# rw-fet-cc-24mm-mk-1_0_1.net
KiCad netlist of a schematic drawn in EAGLE
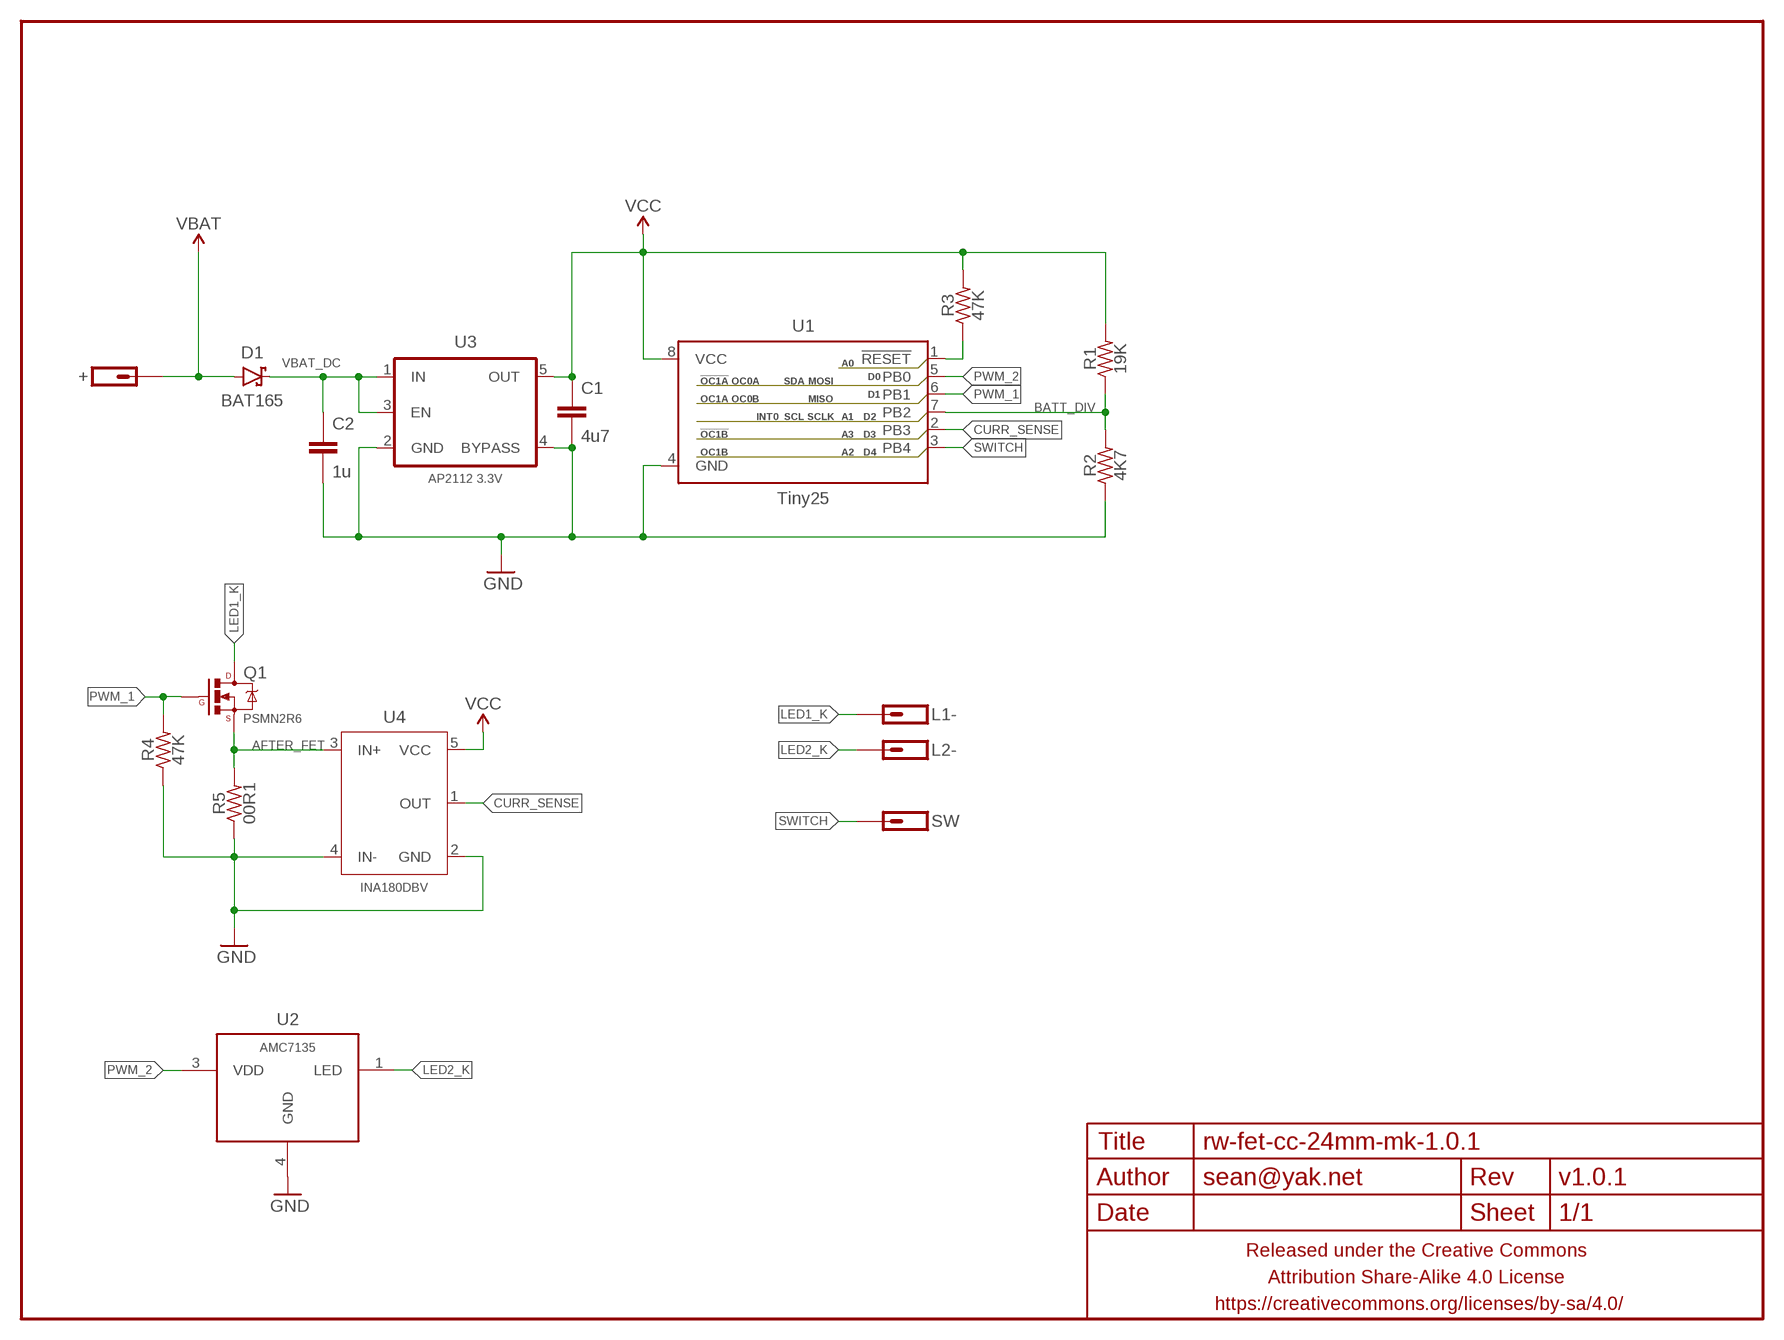
[diagram p0: schematic, sheet 1]

(export (version "E")
  (design (tool "Eeschema 10.0.6"))
  (components
    (comp (ref "+")
      (value "M01PTH-1MM-CIR-NS")
      (footprint "eagle-import:1X01-1MM-CIR-NS")
      (libsource (lib "eagle-import") (part "M01PTH-1MM-CIR-NS"))
    )
    (comp (ref "C1")
      (value "4u7")
      (footprint "eagle-import:C0603-TIGHTER")
      (libsource (lib "eagle-import") (part "CAPACITOR-CERAMICC0603-TIGHTER"))
    )
    (comp (ref "C2")
      (value "1u")
      (footprint "eagle-import:C0402")
      (libsource (lib "eagle-import") (part "CAPACITOR-CERAMICC0402"))
    )
    (comp (ref "D1")
      (value "BAT165")
      (footprint "eagle-import:SOD323-SCHOTTKY")
      (libsource (lib "eagle-import") (part "DIODE-SCHOTTKYSOD323"))
    )
    (comp (ref "FRAME1")
      (value "FRAME-LETTERNO_PACKAGE")
      (footprint "eagle-import:DUMMY")
      (fields (field (name "DESIGNER") "sean@yak.net") (field (name "VERSION") "v1.0.1"))
      (libsource (lib "eagle-import") (part "FRAME-LETTERNO_PACKAGE"))
    )
    (comp (ref "L1-")
      (value "M011X01-0.9MM-CIR")
      (footprint "eagle-import:1X01-0.9MM-CIR")
      (libsource (lib "eagle-import") (part "M011X01-0.9MM-CIR"))
    )
    (comp (ref "L2-")
      (value "M01PTH-0.8MM-CIR")
      (footprint "eagle-import:1X01-0.8MM-CIR")
      (libsource (lib "eagle-import") (part "M01PTH-0.8MM-CIR"))
    )
    (comp (ref "Q1")
      (value "PSMN2R6")
      (footprint "eagle-import:POWERPACK-SO-8")
      (libsource (lib "eagle-import") (part "MOSFET-NCHANNELSIR800DP"))
    )
    (comp (ref "R1")
      (value "19K")
      (footprint "eagle-import:R0402")
      (libsource (lib "eagle-import") (part "RESISTORR0402"))
    )
    (comp (ref "R2")
      (value "4K7")
      (footprint "eagle-import:R0402")
      (libsource (lib "eagle-import") (part "RESISTORR0402"))
    )
    (comp (ref "R3")
      (value "47K")
      (footprint "eagle-import:R0402")
      (libsource (lib "eagle-import") (part "RESISTORR0402"))
    )
    (comp (ref "R4")
      (value "47K")
      (footprint "eagle-import:R0402")
      (libsource (lib "eagle-import") (part "RESISTORR0402"))
    )
    (comp (ref "R5")
      (value "00R1")
      (footprint "eagle-import:R1206")
      (libsource (lib "eagle-import") (part "RESISTORR1206"))
    )
    (comp (ref "SW")
      (value "M01SMD-0.8MM-DIA-NS")
      (footprint "eagle-import:1X01-SMD-0.8MM-DIA-NS")
      (libsource (lib "eagle-import") (part "M01SMD-0.8MM-DIA-NS"))
    )
    (comp (ref "U1")
      (value "Tiny25")
      (footprint "eagle-import:SO08-NARROWER")
      (libsource (lib "eagle-import") (part "ATTINY13SOIC-NARROWPADS"))
    )
    (comp (ref "U2")
      (value "AMC7135")
      (footprint "eagle-import:SOT89-NOTHERM-ROUNDED-LESS")
      (libsource (lib "eagle-import") (part "AMC7135SOT-89-NOTHERM-ROUNDED-LESS"))
    )
    (comp (ref "U3")
      (value "AP2112 3.3V")
      (footprint "eagle-import:SOT23-5")
      (libsource (lib "eagle-import") (part "V_REG_SOT-23-5AP2112"))
    )
    (comp (ref "U4")
      (value "INA180DBV")
      (footprint "eagle-import:SOT23-5")
      (libsource (lib "eagle-import") (part "INA180DBV"))
    )
  )
  (nets
    (net (code "1") (name "/AFTER_FET") (class "Default")
      (node (ref "Q1") (pin "1") (pinfunction "S_1") (pintype "passive"))
      (node (ref "Q1") (pin "2") (pinfunction "S_2") (pintype "passive"))
      (node (ref "Q1") (pin "3") (pinfunction "S_3") (pintype "passive"))
      (node (ref "R5") (pin "2") (pinfunction "2_2") (pintype "passive"))
      (node (ref "U4") (pin "3") (pinfunction "IN+_3") (pintype "bidirectional"))
    )
    (net (code "2") (name "/BATT_DIV") (class "Default")
      (node (ref "R1") (pin "1") (pinfunction "1_1") (pintype "passive"))
      (node (ref "R2") (pin "2") (pinfunction "2_2") (pintype "passive"))
      (node (ref "U1") (pin "7") (pinfunction "PB2_7") (pintype "bidirectional"))
    )
    (net (code "3") (name "/VBAT_DC") (class "Default")
      (node (ref "C2") (pin "1") (pinfunction "1_1") (pintype "passive"))
      (node (ref "D1") (pin "C") (pinfunction "C_C") (pintype "passive"))
      (node (ref "U3") (pin "1") (pinfunction "IN_1") (pintype "input"))
      (node (ref "U3") (pin "3") (pinfunction "EN_3") (pintype "input"))
    )
    (net (code "4") (name "CURR_SENSE") (class "Default")
      (node (ref "U1") (pin "2") (pinfunction "PB3_2") (pintype "bidirectional"))
      (node (ref "U4") (pin "1") (pinfunction "OUT_1") (pintype "bidirectional"))
    )
    (net (code "5") (name "GND") (class "Default")
      (node (ref "C1") (pin "2") (pinfunction "2_2") (pintype "passive"))
      (node (ref "C2") (pin "2") (pinfunction "2_2") (pintype "passive"))
      (node (ref "R2") (pin "1") (pinfunction "1_1") (pintype "passive"))
      (node (ref "R4") (pin "1") (pinfunction "1_1") (pintype "passive"))
      (node (ref "R5") (pin "1") (pinfunction "1_1") (pintype "passive"))
      (node (ref "U1") (pin "4") (pinfunction "GND_4") (pintype "bidirectional"))
      (node (ref "U2") (pin "4") (pinfunction "GND_4") (pintype "bidirectional"))
      (node (ref "U3") (pin "2") (pinfunction "GND_2") (pintype "input"))
      (node (ref "U3") (pin "4") (pinfunction "BYPASS_4") (pintype "input"))
      (node (ref "U4") (pin "2") (pinfunction "GND_2") (pintype "bidirectional"))
      (node (ref "U4") (pin "4") (pinfunction "IN-_4") (pintype "bidirectional"))
    )
    (net (code "6") (name "LED1_K") (class "Default")
      (node (ref "L1-") (pin "P$1") (pinfunction "1_P$1") (pintype "passive"))
      (node (ref "Q1") (pin "5678") (pinfunction "D_5678") (pintype "passive"))
    )
    (net (code "7") (name "LED2_K") (class "Default")
      (node (ref "L2-") (pin "1") (pinfunction "1_1") (pintype "passive"))
      (node (ref "U2") (pin "1") (pinfunction "LED_1") (pintype "bidirectional"))
    )
    (net (code "8") (name "Net-(U1-~{RESET})") (class "Default")
      (node (ref "R3") (pin "1") (pinfunction "1_1") (pintype "passive"))
      (node (ref "U1") (pin "1") (pinfunction "~{RESET}_1") (pintype "bidirectional"))
    )
    (net (code "9") (name "PWM_1") (class "Default")
      (node (ref "Q1") (pin "4") (pinfunction "G_4") (pintype "passive"))
      (node (ref "R4") (pin "2") (pinfunction "2_2") (pintype "passive"))
      (node (ref "U1") (pin "6") (pinfunction "PB1_6") (pintype "bidirectional"))
    )
    (net (code "10") (name "PWM_2") (class "Default")
      (node (ref "U1") (pin "5") (pinfunction "PB0_5") (pintype "bidirectional"))
      (node (ref "U2") (pin "3") (pinfunction "VDD_3") (pintype "bidirectional"))
    )
    (net (code "11") (name "SWITCH") (class "Default")
      (node (ref "SW") (pin "P$1") (pinfunction "1_P$1") (pintype "passive"))
      (node (ref "U1") (pin "3") (pinfunction "PB4_3") (pintype "bidirectional"))
    )
    (net (code "12") (name "VBAT") (class "Default")
      (node (ref "+") (pin "1") (pinfunction "1_1") (pintype "passive"))
      (node (ref "D1") (pin "A") (pinfunction "A_A") (pintype "passive"))
    )
    (net (code "13") (name "VCC") (class "Default")
      (node (ref "C1") (pin "1") (pinfunction "1_1") (pintype "passive"))
      (node (ref "R1") (pin "2") (pinfunction "2_2") (pintype "passive"))
      (node (ref "R3") (pin "2") (pinfunction "2_2") (pintype "passive"))
      (node (ref "U1") (pin "8") (pinfunction "VCC_8") (pintype "bidirectional"))
      (node (ref "U3") (pin "5") (pinfunction "OUT_5") (pintype "passive"))
      (node (ref "U4") (pin "5") (pinfunction "VCC_5") (pintype "bidirectional"))
    )
  )
)
